# cc2530-LR-standalone-router.net
KiCad netlist of a schematic drawn in EAGLE
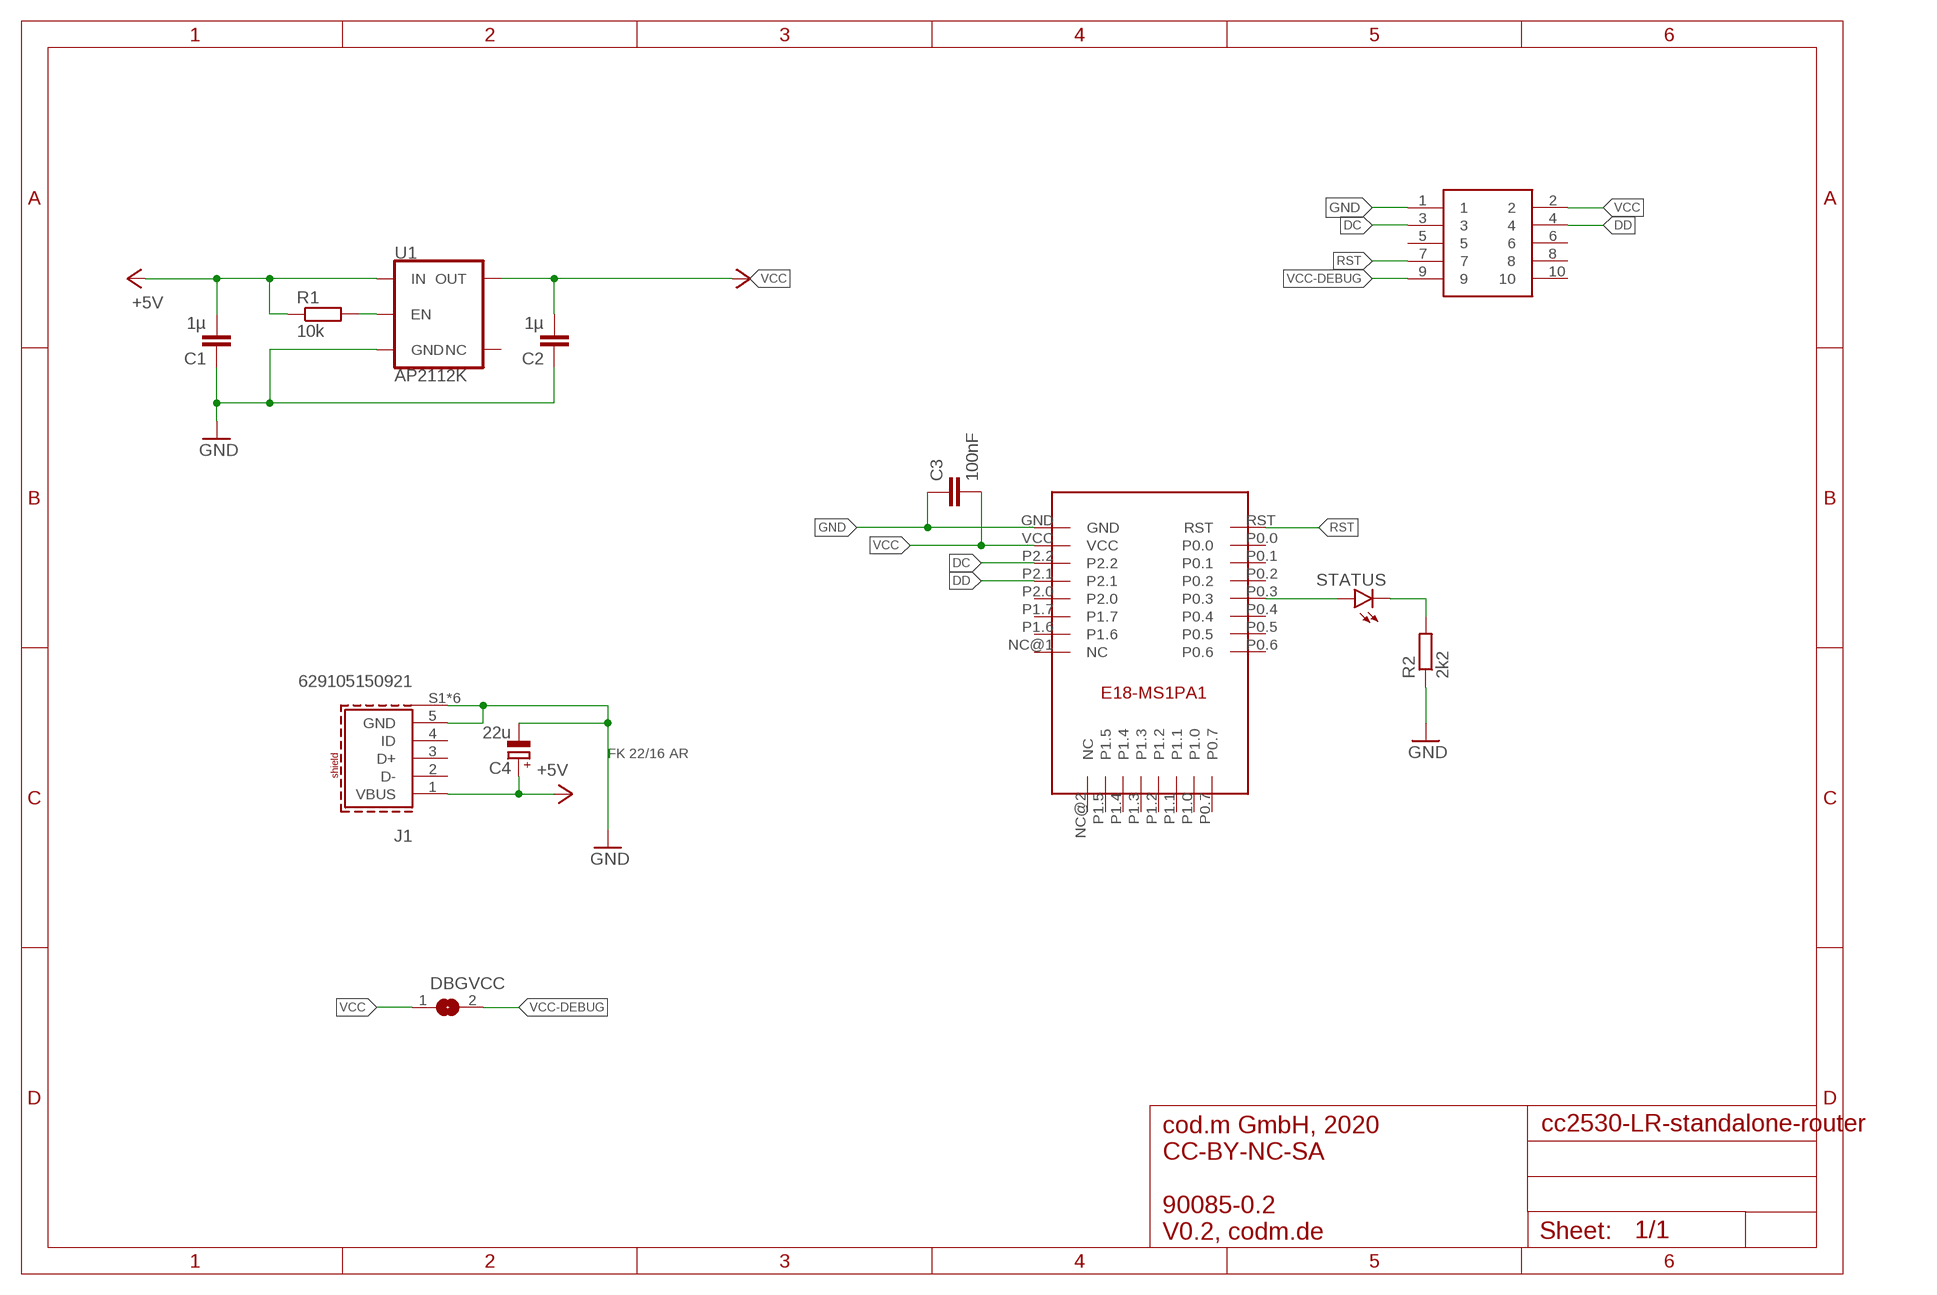
[diagram p0: schematic, sheet 1]

(export (version "E")
  (design (tool "Eeschema 10.0.6"))
  (components
    (comp (ref "C1")
      (value "1µ")
      (footprint "eagle-import:C0805")
      (libsource (lib "eagle-import") (part "C-EUC0805"))
    )
    (comp (ref "C2")
      (value "1µ")
      (footprint "eagle-import:C0805")
      (libsource (lib "eagle-import") (part "C-EUC0805"))
    )
    (comp (ref "C3")
      (value "100nF")
      (footprint "eagle-import:C0805")
      (libsource (lib "eagle-import") (part "C-EUC0805"))
    )
    (comp (ref "C4")
      (value "22u")
      (footprint "eagle-import:PANASONIC_C")
      (libsource (lib "eagle-import") (part "CPOL-EUC"))
    )
    (comp (ref "DBGVCC")
      (value "SJ")
      (footprint "eagle-import:SJ")
      (libsource (lib "eagle-import") (part "SJ"))
    )
    (comp (ref "DEBUG")
      (value "20021121-00010C4LF")
      (footprint "eagle-import:2002112100010C4LF")
      (fields (field (name "MOUSER_PART_NUMBER") "649-202112100010C4LF"))
      (libsource (lib "eagle-import") (part "20021121-00010C4LF"))
    )
    (comp (ref "J1")
      (value "629105150921")
      (footprint "eagle-import:629105150921")
      (libsource (lib "eagle-import") (part "629105150921"))
    )
    (comp (ref "R1")
      (value "10k")
      (footprint "eagle-import:R0805")
      (libsource (lib "eagle-import") (part "R-EU_R0805"))
    )
    (comp (ref "R2")
      (value "2k2")
      (footprint "eagle-import:R0805")
      (libsource (lib "eagle-import") (part "R-EU_R0805"))
    )
    (comp (ref "STATUS")
      (value "LEDCHIPLED_0805")
      (footprint "eagle-import:CHIPLED_0805")
      (libsource (lib "eagle-import") (part "LEDCHIPLED_0805"))
    )
    (comp (ref "U$5")
      (value "E18-MS1PA1IPX")
      (footprint "eagle-import:E18-MS1PA1-IPX")
      (libsource (lib "eagle-import") (part "E18-MS1PA1IPX"))
    )
    (comp (ref "U1")
      (value "AP2112K")
      (footprint "eagle-import:SOT23-5")
      (libsource (lib "eagle-import") (part "V_REG_AP2112K-3.3V"))
    )
  )
  (nets
    (net (code "1") (name "+5V") (class "Default")
      (node (ref "C1") (pin "2") (pinfunction "2_2") (pintype "passive"))
      (node (ref "C4") (pin "+") (pinfunction "+_+") (pintype "passive"))
      (node (ref "J1") (pin "1") (pinfunction "VBUS_1") (pintype "passive"))
      (node (ref "R1") (pin "1") (pinfunction "1_1") (pintype "passive"))
      (node (ref "U1") (pin "1") (pinfunction "IN_1") (pintype "input"))
    )
    (net (code "2") (name "DC") (class "Default")
      (node (ref "DEBUG") (pin "3") (pinfunction "3_3") (pintype "bidirectional"))
      (node (ref "U$5") (pin "P2.2") (pinfunction "P2.2_P2.2") (pintype "bidirectional"))
    )
    (net (code "3") (name "DD") (class "Default")
      (node (ref "DEBUG") (pin "4") (pinfunction "4_4") (pintype "bidirectional"))
      (node (ref "U$5") (pin "P2.1") (pinfunction "P2.1_P2.1") (pintype "bidirectional"))
    )
    (net (code "4") (name "GND") (class "Default")
      (node (ref "C1") (pin "1") (pinfunction "1_1") (pintype "passive"))
      (node (ref "C2") (pin "1") (pinfunction "1_1") (pintype "passive"))
      (node (ref "C3") (pin "1") (pinfunction "1_1") (pintype "passive"))
      (node (ref "C4") (pin "-") (pinfunction "-_-") (pintype "passive"))
      (node (ref "DEBUG") (pin "1") (pinfunction "1_1") (pintype "bidirectional"))
      (node (ref "J1") (pin "5") (pinfunction "GND_5") (pintype "passive"))
      (node (ref "J1") (pin "S1") (pinfunction "SHIELD_S1") (pintype "passive"))
      (node (ref "J1") (pin "S2") (pinfunction "SHIELD_S2") (pintype "passive"))
      (node (ref "J1") (pin "S3") (pinfunction "SHIELD_S3") (pintype "passive"))
      (node (ref "J1") (pin "S4") (pinfunction "SHIELD_S4") (pintype "passive"))
      (node (ref "J1") (pin "S5") (pinfunction "SHIELD_S5") (pintype "passive"))
      (node (ref "J1") (pin "S6") (pinfunction "SHIELD_S6") (pintype "passive"))
      (node (ref "R2") (pin "1") (pinfunction "1_1") (pintype "passive"))
      (node (ref "U$5") (pin "GND") (pinfunction "GND_GND") (pintype "bidirectional"))
      (node (ref "U1") (pin "2") (pinfunction "GND_2") (pintype "input"))
    )
    (net (code "5") (name "Net-(R2-Pad2)") (class "Default")
      (node (ref "R2") (pin "2") (pinfunction "2_2") (pintype "passive"))
      (node (ref "STATUS") (pin "C") (pinfunction "C_C") (pintype "passive"))
    )
    (net (code "6") (name "Net-(STATUS-PadA)") (class "Default")
      (node (ref "STATUS") (pin "A") (pinfunction "A_A") (pintype "passive"))
      (node (ref "U$5") (pin "P0.3") (pinfunction "P0.3_P0.3") (pintype "bidirectional"))
    )
    (net (code "7") (name "Net-(U1-EN)") (class "Default")
      (node (ref "R1") (pin "2") (pinfunction "2_2") (pintype "passive"))
      (node (ref "U1") (pin "3") (pinfunction "EN_3") (pintype "input"))
    )
    (net (code "8") (name "RST") (class "Default")
      (node (ref "DEBUG") (pin "7") (pinfunction "7_7") (pintype "bidirectional"))
      (node (ref "U$5") (pin "RST") (pinfunction "RST_RST") (pintype "bidirectional"))
    )
    (net (code "9") (name "VCC") (class "Default")
      (node (ref "C2") (pin "2") (pinfunction "2_2") (pintype "passive"))
      (node (ref "C3") (pin "2") (pinfunction "2_2") (pintype "passive"))
      (node (ref "DBGVCC") (pin "1") (pinfunction "1_1") (pintype "passive"))
      (node (ref "DEBUG") (pin "2") (pinfunction "2_2") (pintype "bidirectional"))
      (node (ref "U$5") (pin "VCC") (pinfunction "VCC_VCC") (pintype "bidirectional"))
      (node (ref "U1") (pin "5") (pinfunction "OUT_5") (pintype "passive"))
    )
    (net (code "10") (name "VCC-DEBUG") (class "Default")
      (node (ref "DBGVCC") (pin "2") (pinfunction "2_2") (pintype "passive"))
      (node (ref "DEBUG") (pin "9") (pinfunction "9_9") (pintype "bidirectional"))
    )
    (net (code "11") (name "unconnected-(DEBUG-Pad5)") (class "Default")
      (node (ref "DEBUG") (pin "5") (pinfunction "5_5") (pintype "bidirectional"))
    )
    (net (code "12") (name "unconnected-(DEBUG-Pad6)") (class "Default")
      (node (ref "DEBUG") (pin "6") (pinfunction "6_6") (pintype "bidirectional"))
    )
    (net (code "13") (name "unconnected-(DEBUG-Pad8)") (class "Default")
      (node (ref "DEBUG") (pin "8") (pinfunction "8_8") (pintype "bidirectional"))
    )
    (net (code "14") (name "unconnected-(DEBUG-Pad10)") (class "Default")
      (node (ref "DEBUG") (pin "10") (pinfunction "10_10") (pintype "bidirectional"))
    )
    (net (code "15") (name "unconnected-(J1-D+-Pad3)") (class "Default")
      (node (ref "J1") (pin "3") (pinfunction "D+_3") (pintype "passive"))
    )
    (net (code "16") (name "unconnected-(J1-D--Pad2)") (class "Default")
      (node (ref "J1") (pin "2") (pinfunction "D-_2") (pintype "passive"))
    )
    (net (code "17") (name "unconnected-(J1-ID-Pad4)") (class "Default")
      (node (ref "J1") (pin "4") (pinfunction "ID_4") (pintype "passive"))
    )
    (net (code "18") (name "unconnected-(U$5-NC-PadNC@1)") (class "Default")
      (node (ref "U$5") (pin "NC@1") (pinfunction "NC_NC@1") (pintype "bidirectional"))
    )
    (net (code "19") (name "unconnected-(U$5-NC-PadNC@2)") (class "Default")
      (node (ref "U$5") (pin "NC@2") (pinfunction "NC_NC@2") (pintype "bidirectional"))
    )
    (net (code "20") (name "unconnected-(U$5-PadP0.0)") (class "Default")
      (node (ref "U$5") (pin "P0.0") (pinfunction "P0.0_P0.0") (pintype "bidirectional"))
    )
    (net (code "21") (name "unconnected-(U$5-PadP0.1)") (class "Default")
      (node (ref "U$5") (pin "P0.1") (pinfunction "P0.1_P0.1") (pintype "bidirectional"))
    )
    (net (code "22") (name "unconnected-(U$5-PadP0.2)") (class "Default")
      (node (ref "U$5") (pin "P0.2") (pinfunction "P0.2_P0.2") (pintype "bidirectional"))
    )
    (net (code "23") (name "unconnected-(U$5-PadP0.4)") (class "Default")
      (node (ref "U$5") (pin "P0.4") (pinfunction "P0.4_P0.4") (pintype "bidirectional"))
    )
    (net (code "24") (name "unconnected-(U$5-PadP0.5)") (class "Default")
      (node (ref "U$5") (pin "P0.5") (pinfunction "P0.5_P0.5") (pintype "bidirectional"))
    )
    (net (code "25") (name "unconnected-(U$5-PadP0.6)") (class "Default")
      (node (ref "U$5") (pin "P0.6") (pinfunction "P0.6_P0.6") (pintype "bidirectional"))
    )
    (net (code "26") (name "unconnected-(U$5-PadP0.7)") (class "Default")
      (node (ref "U$5") (pin "P0.7") (pinfunction "P0.7_P0.7") (pintype "bidirectional"))
    )
    (net (code "27") (name "unconnected-(U$5-PadP1.0)") (class "Default")
      (node (ref "U$5") (pin "P1.0") (pinfunction "P1.0_P1.0") (pintype "bidirectional"))
    )
    (net (code "28") (name "unconnected-(U$5-PadP1.1)") (class "Default")
      (node (ref "U$5") (pin "P1.1") (pinfunction "P1.1_P1.1") (pintype "bidirectional"))
    )
    (net (code "29") (name "unconnected-(U$5-PadP1.2)") (class "Default")
      (node (ref "U$5") (pin "P1.2") (pinfunction "P1.2_P1.2") (pintype "bidirectional"))
    )
    (net (code "30") (name "unconnected-(U$5-PadP1.3)") (class "Default")
      (node (ref "U$5") (pin "P1.3") (pinfunction "P1.3_P1.3") (pintype "bidirectional"))
    )
    (net (code "31") (name "unconnected-(U$5-PadP1.4)") (class "Default")
      (node (ref "U$5") (pin "P1.4") (pinfunction "P1.4_P1.4") (pintype "bidirectional"))
    )
    (net (code "32") (name "unconnected-(U$5-PadP1.5)") (class "Default")
      (node (ref "U$5") (pin "P1.5") (pinfunction "P1.5_P1.5") (pintype "bidirectional"))
    )
    (net (code "33") (name "unconnected-(U$5-PadP1.6)") (class "Default")
      (node (ref "U$5") (pin "P1.6") (pinfunction "P1.6_P1.6") (pintype "bidirectional"))
    )
    (net (code "34") (name "unconnected-(U$5-PadP1.7)") (class "Default")
      (node (ref "U$5") (pin "P1.7") (pinfunction "P1.7_P1.7") (pintype "bidirectional"))
    )
    (net (code "35") (name "unconnected-(U$5-PadP2.0)") (class "Default")
      (node (ref "U$5") (pin "P2.0") (pinfunction "P2.0_P2.0") (pintype "bidirectional"))
    )
    (net (code "36") (name "unconnected-(U1-NC-Pad4)") (class "Default")
      (node (ref "U1") (pin "4") (pinfunction "NC_4") (pintype "no_connect"))
    )
  )
)
